# PWM_LED_Controller.net
KiCad netlist of a schematic drawn in EAGLE
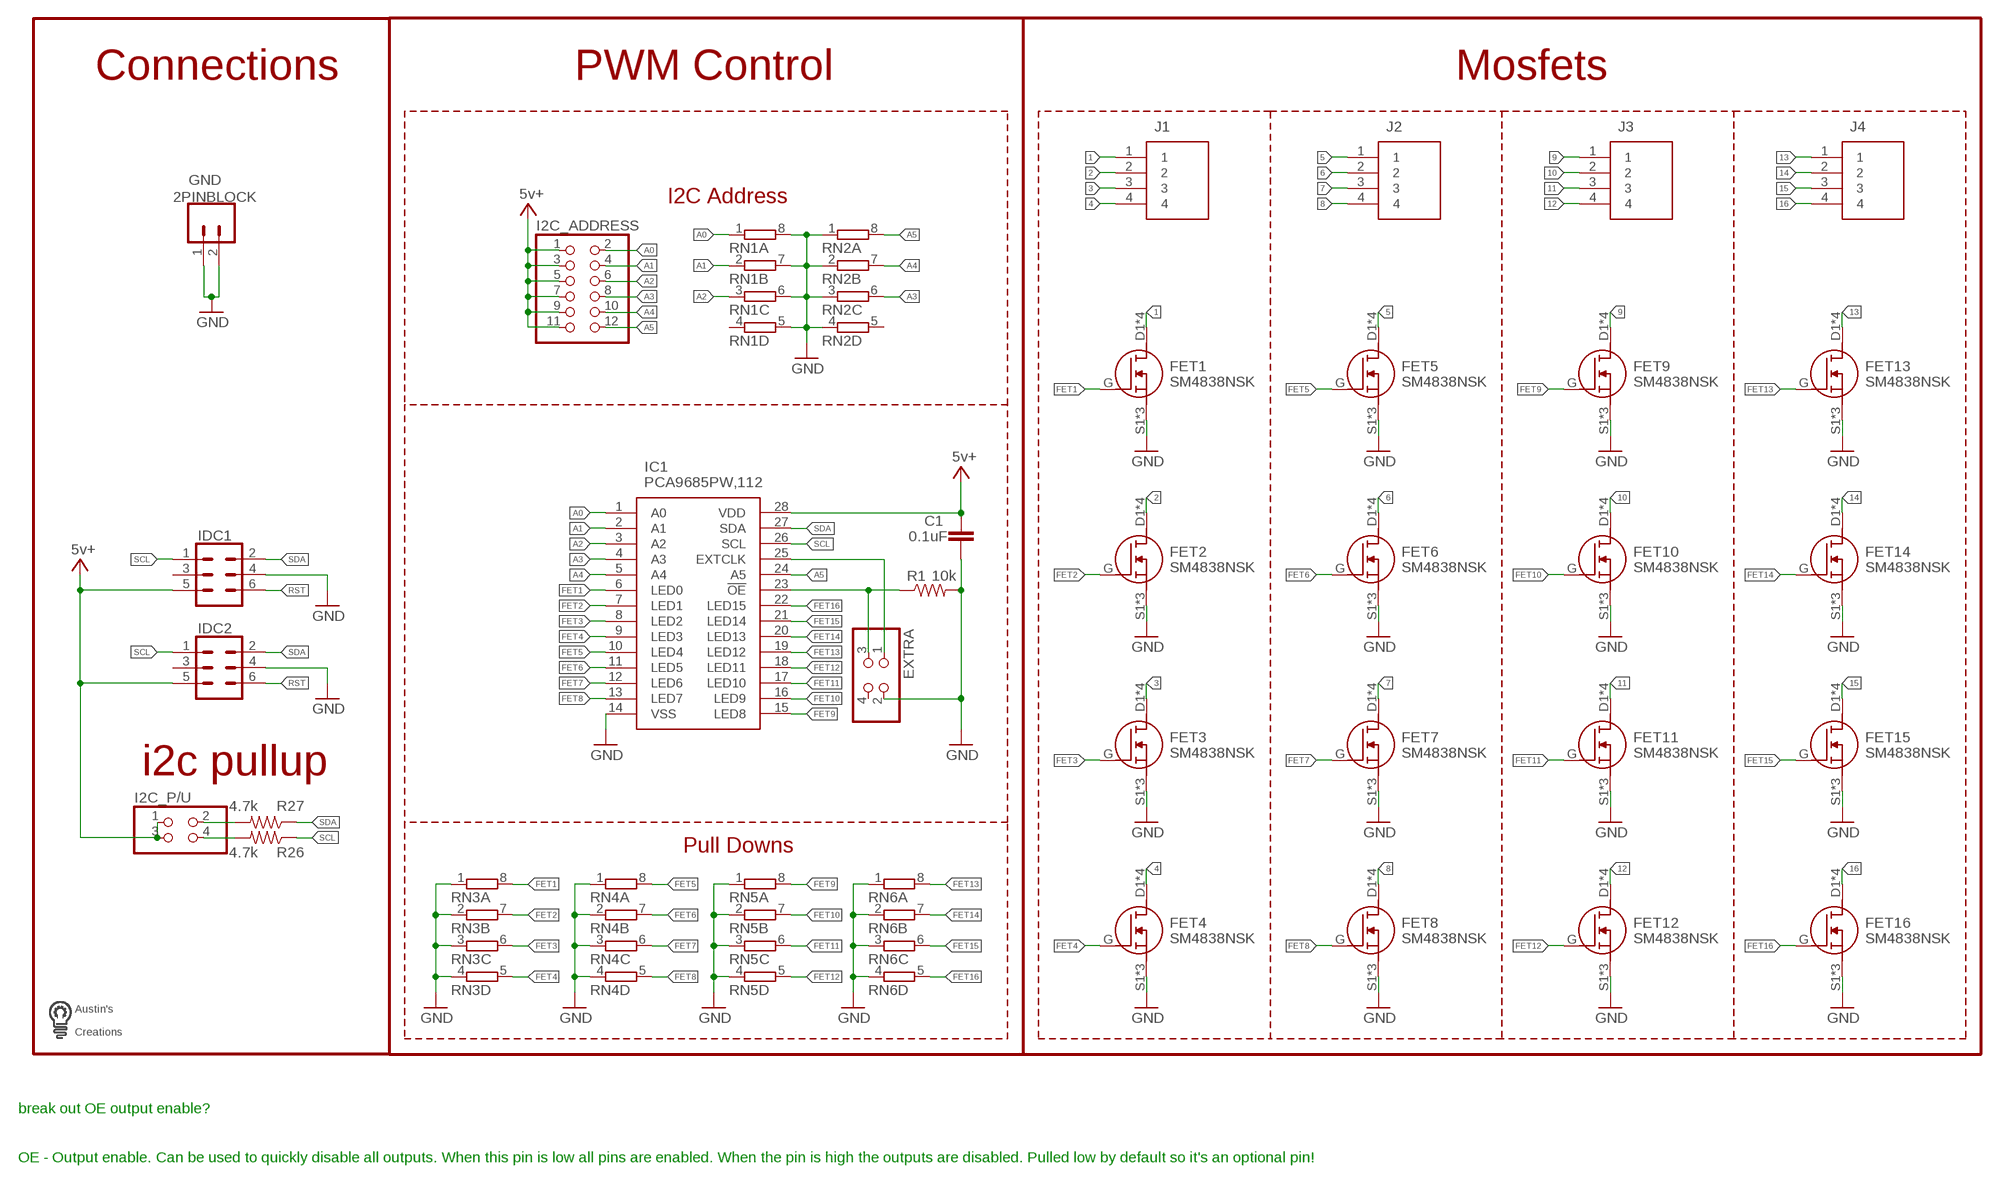
[diagram p0: schematic, sheet 1]

(export (version "E")
  (design (tool "Eeschema 10.0.6"))
  (components
    (comp (ref "C1")
      (value "0.1uF")
      (footprint "eagle-import:C0603")
      (libsource (lib "eagle-import") (part "C-EUC0603"))
    )
    (comp (ref "EXTRA")
      (value "PINHD-2X2")
      (footprint "eagle-import:2X02")
      (libsource (lib "eagle-import") (part "PINHD-2X2"))
    )
    (comp (ref "FET1")
      (value "SM4838NSK")
      (footprint "eagle-import:SM4838NSK")
      (libsource (lib "eagle-import") (part "SM4838NSK"))
    )
    (comp (ref "FET2")
      (value "SM4838NSK")
      (footprint "eagle-import:SM4838NSK")
      (libsource (lib "eagle-import") (part "SM4838NSK"))
    )
    (comp (ref "FET3")
      (value "SM4838NSK")
      (footprint "eagle-import:SM4838NSK")
      (libsource (lib "eagle-import") (part "SM4838NSK"))
    )
    (comp (ref "FET4")
      (value "SM4838NSK")
      (footprint "eagle-import:SM4838NSK")
      (libsource (lib "eagle-import") (part "SM4838NSK"))
    )
    (comp (ref "FET5")
      (value "SM4838NSK")
      (footprint "eagle-import:SM4838NSK")
      (libsource (lib "eagle-import") (part "SM4838NSK"))
    )
    (comp (ref "FET6")
      (value "SM4838NSK")
      (footprint "eagle-import:SM4838NSK")
      (libsource (lib "eagle-import") (part "SM4838NSK"))
    )
    (comp (ref "FET7")
      (value "SM4838NSK")
      (footprint "eagle-import:SM4838NSK")
      (libsource (lib "eagle-import") (part "SM4838NSK"))
    )
    (comp (ref "FET8")
      (value "SM4838NSK")
      (footprint "eagle-import:SM4838NSK")
      (libsource (lib "eagle-import") (part "SM4838NSK"))
    )
    (comp (ref "FET9")
      (value "SM4838NSK")
      (footprint "eagle-import:SM4838NSK")
      (libsource (lib "eagle-import") (part "SM4838NSK"))
    )
    (comp (ref "FET10")
      (value "SM4838NSK")
      (footprint "eagle-import:SM4838NSK")
      (libsource (lib "eagle-import") (part "SM4838NSK"))
    )
    (comp (ref "FET11")
      (value "SM4838NSK")
      (footprint "eagle-import:SM4838NSK")
      (libsource (lib "eagle-import") (part "SM4838NSK"))
    )
    (comp (ref "FET12")
      (value "SM4838NSK")
      (footprint "eagle-import:SM4838NSK")
      (libsource (lib "eagle-import") (part "SM4838NSK"))
    )
    (comp (ref "FET13")
      (value "SM4838NSK")
      (footprint "eagle-import:SM4838NSK")
      (libsource (lib "eagle-import") (part "SM4838NSK"))
    )
    (comp (ref "FET14")
      (value "SM4838NSK")
      (footprint "eagle-import:SM4838NSK")
      (libsource (lib "eagle-import") (part "SM4838NSK"))
    )
    (comp (ref "FET15")
      (value "SM4838NSK")
      (footprint "eagle-import:SM4838NSK")
      (libsource (lib "eagle-import") (part "SM4838NSK"))
    )
    (comp (ref "FET16")
      (value "SM4838NSK")
      (footprint "eagle-import:SM4838NSK")
      (libsource (lib "eagle-import") (part "SM4838NSK"))
    )
    (comp (ref "GND")
      (value "2PINBLOCK")
      (footprint "eagle-import:SCREWTERMINAL-5MM-2")
      (libsource (lib "eagle-import") (part "2PINBLOCK"))
    )
    (comp (ref "I2C_ADDRESS")
      (value "PINHD-2X6")
      (footprint "eagle-import:2X06")
      (libsource (lib "eagle-import") (part "PINHD-2X6"))
    )
    (comp (ref "I2C_P/U")
      (value "PINHD-2X2")
      (footprint "eagle-import:2X02")
      (libsource (lib "eagle-import") (part "PINHD-2X2"))
    )
    (comp (ref "IC1")
      (value "PCA9685PW,112")
      (footprint "eagle-import:SOP65P640X110-28N")
      (fields (field (name "MOUSER_PART_NUMBER") "771-PCA9685PW,112"))
      (libsource (lib "eagle-import") (part "PCA9685PW,112"))
    )
    (comp (ref "IDC1")
      (value "CONN_03X2SHROUD")
      (footprint "eagle-import:2X3-SHROUDED")
      (libsource (lib "eagle-import") (part "CONN_03X2SHROUD"))
    )
    (comp (ref "IDC2")
      (value "CONN_03X2SHROUD")
      (footprint "eagle-import:2X3-SHROUDED")
      (libsource (lib "eagle-import") (part "CONN_03X2SHROUD"))
    )
    (comp (ref "J1")
      (value "SCREWTERMINAL-4P-5MM")
      (footprint "eagle-import:SCREWTERMINAL-4P-5MM")
      (fields
        (field (name "MANUFACTURER_PART_NUMBER") "TB001-500-04BE")
        (field (name "MOUSER_PART_NUMBER") "490-TB001-500-04BE")
      )
      (libsource (lib "eagle-import") (part "SCREWTERMINAL-4P-5MM"))
    )
    (comp (ref "J2")
      (value "SCREWTERMINAL-4P-5MM")
      (footprint "eagle-import:SCREWTERMINAL-4P-5MM")
      (fields
        (field (name "MANUFACTURER_PART_NUMBER") "TB001-500-04BE")
        (field (name "MOUSER_PART_NUMBER") "490-TB001-500-04BE")
      )
      (libsource (lib "eagle-import") (part "SCREWTERMINAL-4P-5MM"))
    )
    (comp (ref "J3")
      (value "SCREWTERMINAL-4P-5MM")
      (footprint "eagle-import:SCREWTERMINAL-4P-5MM")
      (fields
        (field (name "MANUFACTURER_PART_NUMBER") "TB001-500-04BE")
        (field (name "MOUSER_PART_NUMBER") "490-TB001-500-04BE")
      )
      (libsource (lib "eagle-import") (part "SCREWTERMINAL-4P-5MM"))
    )
    (comp (ref "J4")
      (value "SCREWTERMINAL-4P-5MM")
      (footprint "eagle-import:SCREWTERMINAL-4P-5MM")
      (fields
        (field (name "MANUFACTURER_PART_NUMBER") "TB001-500-04BE")
        (field (name "MOUSER_PART_NUMBER") "490-TB001-500-04BE")
      )
      (libsource (lib "eagle-import") (part "SCREWTERMINAL-4P-5MM"))
    )
    (comp (ref "R1")
      (value "10k")
      (footprint "eagle-import:R0603")
      (libsource (lib "eagle-import") (part "R-US_R0603"))
    )
    (comp (ref "R26")
      (value "4.7k")
      (footprint "eagle-import:R0603")
      (libsource (lib "eagle-import") (part "R-US_R0603"))
    )
    (comp (ref "R27")
      (value "4.7k")
      (footprint "eagle-import:R0603")
      (libsource (lib "eagle-import") (part "R-US_R0603"))
    )
    (comp (ref "RN1")
      (value "4R-N0603-ARC")
      (footprint "eagle-import:0603-ARC")
      (libsource (lib "eagle-import") (part "4R-N0603-ARC"))
    )
    (comp (ref "RN2")
      (value "4R-N0603-ARC")
      (footprint "eagle-import:0603-ARC")
      (libsource (lib "eagle-import") (part "4R-N0603-ARC"))
    )
    (comp (ref "RN3")
      (value "4R-N0603-ARC")
      (footprint "eagle-import:0603-ARC")
      (libsource (lib "eagle-import") (part "4R-N0603-ARC"))
    )
    (comp (ref "RN4")
      (value "4R-N0603-ARC")
      (footprint "eagle-import:0603-ARC")
      (libsource (lib "eagle-import") (part "4R-N0603-ARC"))
    )
    (comp (ref "RN5")
      (value "4R-N0603-ARC")
      (footprint "eagle-import:0603-ARC")
      (libsource (lib "eagle-import") (part "4R-N0603-ARC"))
    )
    (comp (ref "RN6")
      (value "4R-N0603-ARC")
      (footprint "eagle-import:0603-ARC")
      (libsource (lib "eagle-import") (part "4R-N0603-ARC"))
    )
    (comp (ref "U$1")
      (value "LOGOMED")
      (footprint "eagle-import:LOGOMED")
      (libsource (lib "eagle-import") (part "LOGOMED"))
    )
  )
  (nets
    (net (code "1") (name "1") (class "Default")
      (node (ref "FET1") (pin "D1") (pinfunction "D_D1") (pintype "bidirectional"))
      (node (ref "FET1") (pin "D2") (pinfunction "D_D2") (pintype "bidirectional"))
      (node (ref "FET1") (pin "D3") (pinfunction "D_D3") (pintype "bidirectional"))
      (node (ref "FET1") (pin "D4") (pinfunction "D_D4") (pintype "bidirectional"))
      (node (ref "J1") (pin "1") (pinfunction "1_1") (pintype "bidirectional"))
    )
    (net (code "2") (name "2") (class "Default")
      (node (ref "FET2") (pin "D1") (pinfunction "D_D1") (pintype "bidirectional"))
      (node (ref "FET2") (pin "D2") (pinfunction "D_D2") (pintype "bidirectional"))
      (node (ref "FET2") (pin "D3") (pinfunction "D_D3") (pintype "bidirectional"))
      (node (ref "FET2") (pin "D4") (pinfunction "D_D4") (pintype "bidirectional"))
      (node (ref "J1") (pin "2") (pinfunction "2_2") (pintype "bidirectional"))
    )
    (net (code "3") (name "3") (class "Default")
      (node (ref "FET3") (pin "D1") (pinfunction "D_D1") (pintype "bidirectional"))
      (node (ref "FET3") (pin "D2") (pinfunction "D_D2") (pintype "bidirectional"))
      (node (ref "FET3") (pin "D3") (pinfunction "D_D3") (pintype "bidirectional"))
      (node (ref "FET3") (pin "D4") (pinfunction "D_D4") (pintype "bidirectional"))
      (node (ref "J1") (pin "3") (pinfunction "3_3") (pintype "bidirectional"))
    )
    (net (code "4") (name "4") (class "Default")
      (node (ref "FET4") (pin "D1") (pinfunction "D_D1") (pintype "bidirectional"))
      (node (ref "FET4") (pin "D2") (pinfunction "D_D2") (pintype "bidirectional"))
      (node (ref "FET4") (pin "D3") (pinfunction "D_D3") (pintype "bidirectional"))
      (node (ref "FET4") (pin "D4") (pinfunction "D_D4") (pintype "bidirectional"))
      (node (ref "J1") (pin "4") (pinfunction "4_4") (pintype "bidirectional"))
    )
    (net (code "5") (name "5") (class "Default")
      (node (ref "FET5") (pin "D1") (pinfunction "D_D1") (pintype "bidirectional"))
      (node (ref "FET5") (pin "D2") (pinfunction "D_D2") (pintype "bidirectional"))
      (node (ref "FET5") (pin "D3") (pinfunction "D_D3") (pintype "bidirectional"))
      (node (ref "FET5") (pin "D4") (pinfunction "D_D4") (pintype "bidirectional"))
      (node (ref "J2") (pin "1") (pinfunction "1_1") (pintype "bidirectional"))
    )
    (net (code "6") (name "5v+") (class "Default")
      (node (ref "C1") (pin "1") (pinfunction "1_1") (pintype "passive"))
      (node (ref "I2C_ADDRESS") (pin "1") (pinfunction "1_1") (pintype "passive"))
      (node (ref "I2C_ADDRESS") (pin "11") (pinfunction "11_11") (pintype "passive"))
      (node (ref "I2C_ADDRESS") (pin "3") (pinfunction "3_3") (pintype "passive"))
      (node (ref "I2C_ADDRESS") (pin "5") (pinfunction "5_5") (pintype "passive"))
      (node (ref "I2C_ADDRESS") (pin "7") (pinfunction "7_7") (pintype "passive"))
      (node (ref "I2C_ADDRESS") (pin "9") (pinfunction "9_9") (pintype "passive"))
      (node (ref "I2C_P/U") (pin "1") (pinfunction "1_1") (pintype "passive"))
      (node (ref "I2C_P/U") (pin "3") (pinfunction "3_3") (pintype "passive"))
      (node (ref "IC1") (pin "28") (pinfunction "VDD_28") (pintype "bidirectional"))
      (node (ref "IDC1") (pin "5") (pinfunction "5_5") (pintype "bidirectional"))
      (node (ref "IDC2") (pin "5") (pinfunction "5_5") (pintype "bidirectional"))
    )
    (net (code "7") (name "6") (class "Default")
      (node (ref "FET6") (pin "D1") (pinfunction "D_D1") (pintype "bidirectional"))
      (node (ref "FET6") (pin "D2") (pinfunction "D_D2") (pintype "bidirectional"))
      (node (ref "FET6") (pin "D3") (pinfunction "D_D3") (pintype "bidirectional"))
      (node (ref "FET6") (pin "D4") (pinfunction "D_D4") (pintype "bidirectional"))
      (node (ref "J2") (pin "2") (pinfunction "2_2") (pintype "bidirectional"))
    )
    (net (code "8") (name "7") (class "Default")
      (node (ref "FET7") (pin "D1") (pinfunction "D_D1") (pintype "bidirectional"))
      (node (ref "FET7") (pin "D2") (pinfunction "D_D2") (pintype "bidirectional"))
      (node (ref "FET7") (pin "D3") (pinfunction "D_D3") (pintype "bidirectional"))
      (node (ref "FET7") (pin "D4") (pinfunction "D_D4") (pintype "bidirectional"))
      (node (ref "J2") (pin "3") (pinfunction "3_3") (pintype "bidirectional"))
    )
    (net (code "9") (name "8") (class "Default")
      (node (ref "FET8") (pin "D1") (pinfunction "D_D1") (pintype "bidirectional"))
      (node (ref "FET8") (pin "D2") (pinfunction "D_D2") (pintype "bidirectional"))
      (node (ref "FET8") (pin "D3") (pinfunction "D_D3") (pintype "bidirectional"))
      (node (ref "FET8") (pin "D4") (pinfunction "D_D4") (pintype "bidirectional"))
      (node (ref "J2") (pin "4") (pinfunction "4_4") (pintype "bidirectional"))
    )
    (net (code "10") (name "9") (class "Default")
      (node (ref "FET9") (pin "D1") (pinfunction "D_D1") (pintype "bidirectional"))
      (node (ref "FET9") (pin "D2") (pinfunction "D_D2") (pintype "bidirectional"))
      (node (ref "FET9") (pin "D3") (pinfunction "D_D3") (pintype "bidirectional"))
      (node (ref "FET9") (pin "D4") (pinfunction "D_D4") (pintype "bidirectional"))
      (node (ref "J3") (pin "1") (pinfunction "1_1") (pintype "bidirectional"))
    )
    (net (code "11") (name "10") (class "Default")
      (node (ref "FET10") (pin "D1") (pinfunction "D_D1") (pintype "bidirectional"))
      (node (ref "FET10") (pin "D2") (pinfunction "D_D2") (pintype "bidirectional"))
      (node (ref "FET10") (pin "D3") (pinfunction "D_D3") (pintype "bidirectional"))
      (node (ref "FET10") (pin "D4") (pinfunction "D_D4") (pintype "bidirectional"))
      (node (ref "J3") (pin "2") (pinfunction "2_2") (pintype "bidirectional"))
    )
    (net (code "12") (name "11") (class "Default")
      (node (ref "FET11") (pin "D1") (pinfunction "D_D1") (pintype "bidirectional"))
      (node (ref "FET11") (pin "D2") (pinfunction "D_D2") (pintype "bidirectional"))
      (node (ref "FET11") (pin "D3") (pinfunction "D_D3") (pintype "bidirectional"))
      (node (ref "FET11") (pin "D4") (pinfunction "D_D4") (pintype "bidirectional"))
      (node (ref "J3") (pin "3") (pinfunction "3_3") (pintype "bidirectional"))
    )
    (net (code "13") (name "12") (class "Default")
      (node (ref "FET12") (pin "D1") (pinfunction "D_D1") (pintype "bidirectional"))
      (node (ref "FET12") (pin "D2") (pinfunction "D_D2") (pintype "bidirectional"))
      (node (ref "FET12") (pin "D3") (pinfunction "D_D3") (pintype "bidirectional"))
      (node (ref "FET12") (pin "D4") (pinfunction "D_D4") (pintype "bidirectional"))
      (node (ref "J3") (pin "4") (pinfunction "4_4") (pintype "bidirectional"))
    )
    (net (code "14") (name "13") (class "Default")
      (node (ref "FET13") (pin "D1") (pinfunction "D_D1") (pintype "bidirectional"))
      (node (ref "FET13") (pin "D2") (pinfunction "D_D2") (pintype "bidirectional"))
      (node (ref "FET13") (pin "D3") (pinfunction "D_D3") (pintype "bidirectional"))
      (node (ref "FET13") (pin "D4") (pinfunction "D_D4") (pintype "bidirectional"))
      (node (ref "J4") (pin "1") (pinfunction "1_1") (pintype "bidirectional"))
    )
    (net (code "15") (name "14") (class "Default")
      (node (ref "FET14") (pin "D1") (pinfunction "D_D1") (pintype "bidirectional"))
      (node (ref "FET14") (pin "D2") (pinfunction "D_D2") (pintype "bidirectional"))
      (node (ref "FET14") (pin "D3") (pinfunction "D_D3") (pintype "bidirectional"))
      (node (ref "FET14") (pin "D4") (pinfunction "D_D4") (pintype "bidirectional"))
      (node (ref "J4") (pin "2") (pinfunction "2_2") (pintype "bidirectional"))
    )
    (net (code "16") (name "15") (class "Default")
      (node (ref "FET15") (pin "D1") (pinfunction "D_D1") (pintype "bidirectional"))
      (node (ref "FET15") (pin "D2") (pinfunction "D_D2") (pintype "bidirectional"))
      (node (ref "FET15") (pin "D3") (pinfunction "D_D3") (pintype "bidirectional"))
      (node (ref "FET15") (pin "D4") (pinfunction "D_D4") (pintype "bidirectional"))
      (node (ref "J4") (pin "3") (pinfunction "3_3") (pintype "bidirectional"))
    )
    (net (code "17") (name "16") (class "Default")
      (node (ref "FET16") (pin "D1") (pinfunction "D_D1") (pintype "bidirectional"))
      (node (ref "FET16") (pin "D2") (pinfunction "D_D2") (pintype "bidirectional"))
      (node (ref "FET16") (pin "D3") (pinfunction "D_D3") (pintype "bidirectional"))
      (node (ref "FET16") (pin "D4") (pinfunction "D_D4") (pintype "bidirectional"))
      (node (ref "J4") (pin "4") (pinfunction "4_4") (pintype "bidirectional"))
    )
    (net (code "18") (name "A0") (class "Default")
      (node (ref "I2C_ADDRESS") (pin "2") (pinfunction "2_2") (pintype "passive"))
      (node (ref "IC1") (pin "1") (pinfunction "A0_1") (pintype "bidirectional"))
      (node (ref "RN1") (pin "1") (pinfunction "1_1") (pintype "passive"))
    )
    (net (code "19") (name "A1") (class "Default")
      (node (ref "I2C_ADDRESS") (pin "4") (pinfunction "4_4") (pintype "passive"))
      (node (ref "IC1") (pin "2") (pinfunction "A1_2") (pintype "bidirectional"))
      (node (ref "RN1") (pin "2") (pinfunction "1_2") (pintype "passive"))
    )
    (net (code "20") (name "A2") (class "Default")
      (node (ref "I2C_ADDRESS") (pin "6") (pinfunction "6_6") (pintype "passive"))
      (node (ref "IC1") (pin "3") (pinfunction "A2_3") (pintype "bidirectional"))
      (node (ref "RN1") (pin "3") (pinfunction "1_3") (pintype "passive"))
    )
    (net (code "21") (name "A3") (class "Default")
      (node (ref "I2C_ADDRESS") (pin "8") (pinfunction "8_8") (pintype "passive"))
      (node (ref "IC1") (pin "4") (pinfunction "A3_4") (pintype "bidirectional"))
      (node (ref "RN2") (pin "6") (pinfunction "2_6") (pintype "passive"))
    )
    (net (code "22") (name "A4") (class "Default")
      (node (ref "I2C_ADDRESS") (pin "10") (pinfunction "10_10") (pintype "passive"))
      (node (ref "IC1") (pin "5") (pinfunction "A4_5") (pintype "bidirectional"))
      (node (ref "RN2") (pin "7") (pinfunction "2_7") (pintype "passive"))
    )
    (net (code "23") (name "A5") (class "Default")
      (node (ref "I2C_ADDRESS") (pin "12") (pinfunction "12_12") (pintype "passive"))
      (node (ref "IC1") (pin "24") (pinfunction "A5_24") (pintype "bidirectional"))
      (node (ref "RN2") (pin "8") (pinfunction "2_8") (pintype "passive"))
    )
    (net (code "24") (name "FET1") (class "Default")
      (node (ref "FET1") (pin "G") (pinfunction "G_G") (pintype "bidirectional"))
      (node (ref "IC1") (pin "6") (pinfunction "LED0_6") (pintype "bidirectional"))
      (node (ref "RN3") (pin "8") (pinfunction "2_8") (pintype "passive"))
    )
    (net (code "25") (name "FET2") (class "Default")
      (node (ref "FET2") (pin "G") (pinfunction "G_G") (pintype "bidirectional"))
      (node (ref "IC1") (pin "7") (pinfunction "LED1_7") (pintype "bidirectional"))
      (node (ref "RN3") (pin "7") (pinfunction "2_7") (pintype "passive"))
    )
    (net (code "26") (name "FET3") (class "Default")
      (node (ref "FET3") (pin "G") (pinfunction "G_G") (pintype "bidirectional"))
      (node (ref "IC1") (pin "8") (pinfunction "LED2_8") (pintype "bidirectional"))
      (node (ref "RN3") (pin "6") (pinfunction "2_6") (pintype "passive"))
    )
    (net (code "27") (name "FET4") (class "Default")
      (node (ref "FET4") (pin "G") (pinfunction "G_G") (pintype "bidirectional"))
      (node (ref "IC1") (pin "9") (pinfunction "LED3_9") (pintype "bidirectional"))
      (node (ref "RN3") (pin "5") (pinfunction "2_5") (pintype "passive"))
    )
    (net (code "28") (name "FET5") (class "Default")
      (node (ref "FET5") (pin "G") (pinfunction "G_G") (pintype "bidirectional"))
      (node (ref "IC1") (pin "10") (pinfunction "LED4_10") (pintype "bidirectional"))
      (node (ref "RN4") (pin "8") (pinfunction "2_8") (pintype "passive"))
    )
    (net (code "29") (name "FET6") (class "Default")
      (node (ref "FET6") (pin "G") (pinfunction "G_G") (pintype "bidirectional"))
      (node (ref "IC1") (pin "11") (pinfunction "LED5_11") (pintype "bidirectional"))
      (node (ref "RN4") (pin "7") (pinfunction "2_7") (pintype "passive"))
    )
    (net (code "30") (name "FET7") (class "Default")
      (node (ref "FET7") (pin "G") (pinfunction "G_G") (pintype "bidirectional"))
      (node (ref "IC1") (pin "12") (pinfunction "LED6_12") (pintype "bidirectional"))
      (node (ref "RN4") (pin "6") (pinfunction "2_6") (pintype "passive"))
    )
    (net (code "31") (name "FET8") (class "Default")
      (node (ref "FET8") (pin "G") (pinfunction "G_G") (pintype "bidirectional"))
      (node (ref "IC1") (pin "13") (pinfunction "LED7_13") (pintype "bidirectional"))
      (node (ref "RN4") (pin "5") (pinfunction "2_5") (pintype "passive"))
    )
    (net (code "32") (name "FET9") (class "Default")
      (node (ref "FET9") (pin "G") (pinfunction "G_G") (pintype "bidirectional"))
      (node (ref "IC1") (pin "15") (pinfunction "LED8_15") (pintype "bidirectional"))
      (node (ref "RN5") (pin "8") (pinfunction "2_8") (pintype "passive"))
    )
    (net (code "33") (name "FET10") (class "Default")
      (node (ref "FET10") (pin "G") (pinfunction "G_G") (pintype "bidirectional"))
      (node (ref "IC1") (pin "16") (pinfunction "LED9_16") (pintype "bidirectional"))
      (node (ref "RN5") (pin "7") (pinfunction "2_7") (pintype "passive"))
    )
    (net (code "34") (name "FET11") (class "Default")
      (node (ref "FET11") (pin "G") (pinfunction "G_G") (pintype "bidirectional"))
      (node (ref "IC1") (pin "17") (pinfunction "LED10_17") (pintype "bidirectional"))
      (node (ref "RN5") (pin "6") (pinfunction "2_6") (pintype "passive"))
    )
    (net (code "35") (name "FET12") (class "Default")
      (node (ref "FET12") (pin "G") (pinfunction "G_G") (pintype "bidirectional"))
      (node (ref "IC1") (pin "18") (pinfunction "LED11_18") (pintype "bidirectional"))
      (node (ref "RN5") (pin "5") (pinfunction "2_5") (pintype "passive"))
    )
    (net (code "36") (name "FET13") (class "Default")
      (node (ref "FET13") (pin "G") (pinfunction "G_G") (pintype "bidirectional"))
      (node (ref "IC1") (pin "19") (pinfunction "LED12_19") (pintype "bidirectional"))
      (node (ref "RN6") (pin "8") (pinfunction "2_8") (pintype "passive"))
    )
    (net (code "37") (name "FET14") (class "Default")
      (node (ref "FET14") (pin "G") (pinfunction "G_G") (pintype "bidirectional"))
      (node (ref "IC1") (pin "20") (pinfunction "LED13_20") (pintype "bidirectional"))
      (node (ref "RN6") (pin "7") (pinfunction "2_7") (pintype "passive"))
    )
    (net (code "38") (name "FET15") (class "Default")
      (node (ref "FET15") (pin "G") (pinfunction "G_G") (pintype "bidirectional"))
      (node (ref "IC1") (pin "21") (pinfunction "LED14_21") (pintype "bidirectional"))
      (node (ref "RN6") (pin "6") (pinfunction "2_6") (pintype "passive"))
    )
    (net (code "39") (name "FET16") (class "Default")
      (node (ref "FET16") (pin "G") (pinfunction "G_G") (pintype "bidirectional"))
      (node (ref "IC1") (pin "22") (pinfunction "LED15_22") (pintype "bidirectional"))
      (node (ref "RN6") (pin "5") (pinfunction "2_5") (pintype "passive"))
    )
    (net (code "40") (name "GND") (class "Default")
      (node (ref "C1") (pin "2") (pinfunction "2_2") (pintype "passive"))
      (node (ref "EXTRA") (pin "2") (pinfunction "2_2") (pintype "passive"))
      (node (ref "FET1") (pin "S1") (pinfunction "S_S1") (pintype "bidirectional"))
      (node (ref "FET1") (pin "S2") (pinfunction "S_S2") (pintype "bidirectional"))
      (node (ref "FET1") (pin "S3") (pinfunction "S_S3") (pintype "bidirectional"))
      (node (ref "FET10") (pin "S1") (pinfunction "S_S1") (pintype "bidirectional"))
      (node (ref "FET10") (pin "S2") (pinfunction "S_S2") (pintype "bidirectional"))
      (node (ref "FET10") (pin "S3") (pinfunction "S_S3") (pintype "bidirectional"))
      (node (ref "FET11") (pin "S1") (pinfunction "S_S1") (pintype "bidirectional"))
      (node (ref "FET11") (pin "S2") (pinfunction "S_S2") (pintype "bidirectional"))
      (node (ref "FET11") (pin "S3") (pinfunction "S_S3") (pintype "bidirectional"))
      (node (ref "FET12") (pin "S1") (pinfunction "S_S1") (pintype "bidirectional"))
      (node (ref "FET12") (pin "S2") (pinfunction "S_S2") (pintype "bidirectional"))
      (node (ref "FET12") (pin "S3") (pinfunction "S_S3") (pintype "bidirectional"))
      (node (ref "FET13") (pin "S1") (pinfunction "S_S1") (pintype "bidirectional"))
      (node (ref "FET13") (pin "S2") (pinfunction "S_S2") (pintype "bidirectional"))
      (node (ref "FET13") (pin "S3") (pinfunction "S_S3") (pintype "bidirectional"))
      (node (ref "FET14") (pin "S1") (pinfunction "S_S1") (pintype "bidirectional"))
      (node (ref "FET14") (pin "S2") (pinfunction "S_S2") (pintype "bidirectional"))
      (node (ref "FET14") (pin "S3") (pinfunction "S_S3") (pintype "bidirectional"))
      (node (ref "FET15") (pin "S1") (pinfunction "S_S1") (pintype "bidirectional"))
      (node (ref "FET15") (pin "S2") (pinfunction "S_S2") (pintype "bidirectional"))
      (node (ref "FET15") (pin "S3") (pinfunction "S_S3") (pintype "bidirectional"))
      (node (ref "FET16") (pin "S1") (pinfunction "S_S1") (pintype "bidirectional"))
      (node (ref "FET16") (pin "S2") (pinfunction "S_S2") (pintype "bidirectional"))
      (node (ref "FET16") (pin "S3") (pinfunction "S_S3") (pintype "bidirectional"))
      (node (ref "FET2") (pin "S1") (pinfunction "S_S1") (pintype "bidirectional"))
      (node (ref "FET2") (pin "S2") (pinfunction "S_S2") (pintype "bidirectional"))
      (node (ref "FET2") (pin "S3") (pinfunction "S_S3") (pintype "bidirectional"))
      (node (ref "FET3") (pin "S1") (pinfunction "S_S1") (pintype "bidirectional"))
      (node (ref "FET3") (pin "S2") (pinfunction "S_S2") (pintype "bidirectional"))
      (node (ref "FET3") (pin "S3") (pinfunction "S_S3") (pintype "bidirectional"))
      (node (ref "FET4") (pin "S1") (pinfunction "S_S1") (pintype "bidirectional"))
      (node (ref "FET4") (pin "S2") (pinfunction "S_S2") (pintype "bidirectional"))
      (node (ref "FET4") (pin "S3") (pinfunction "S_S3") (pintype "bidirectional"))
      (node (ref "FET5") (pin "S1") (pinfunction "S_S1") (pintype "bidirectional"))
      (node (ref "FET5") (pin "S2") (pinfunction "S_S2") (pintype "bidirectional"))
      (node (ref "FET5") (pin "S3") (pinfunction "S_S3") (pintype "bidirectional"))
      (node (ref "FET6") (pin "S1") (pinfunction "S_S1") (pintype "bidirectional"))
      (node (ref "FET6") (pin "S2") (pinfunction "S_S2") (pintype "bidirectional"))
      (node (ref "FET6") (pin "S3") (pinfunction "S_S3") (pintype "bidirectional"))
      (node (ref "FET7") (pin "S1") (pinfunction "S_S1") (pintype "bidirectional"))
      (node (ref "FET7") (pin "S2") (pinfunction "S_S2") (pintype "bidirectional"))
      (node (ref "FET7") (pin "S3") (pinfunction "S_S3") (pintype "bidirectional"))
      (node (ref "FET8") (pin "S1") (pinfunction "S_S1") (pintype "bidirectional"))
      (node (ref "FET8") (pin "S2") (pinfunction "S_S2") (pintype "bidirectional"))
      (node (ref "FET8") (pin "S3") (pinfunction "S_S3") (pintype "bidirectional"))
      (node (ref "FET9") (pin "S1") (pinfunction "S_S1") (pintype "bidirectional"))
      (node (ref "FET9") (pin "S2") (pinfunction "S_S2") (pintype "bidirectional"))
      (node (ref "FET9") (pin "S3") (pinfunction "S_S3") (pintype "bidirectional"))
      (node (ref "GND") (pin "1") (pinfunction "1_1") (pintype "passive"))
      (node (ref "GND") (pin "2") (pinfunction "2_2") (pintype "passive"))
      (node (ref "IC1") (pin "14") (pinfunction "VSS_14") (pintype "bidirectional"))
      (node (ref "IDC1") (pin "4") (pinfunction "4_4") (pintype "bidirectional"))
      (node (ref "IDC2") (pin "4") (pinfunction "4_4") (pintype "bidirectional"))
      (node (ref "R1") (pin "2") (pinfunction "2_2") (pintype "passive"))
      (node (ref "RN1") (pin "5") (pinfunction "2_5") (pintype "passive"))
      (node (ref "RN1") (pin "6") (pinfunction "2_6") (pintype "passive"))
      (node (ref "RN1") (pin "7") (pinfunction "2_7") (pintype "passive"))
      (node (ref "RN1") (pin "8") (pinfunction "2_8") (pintype "passive"))
      (node (ref "RN2") (pin "1") (pinfunction "1_1") (pintype "passive"))
      (node (ref "RN2") (pin "2") (pinfunction "1_2") (pintype "passive"))
      (node (ref "RN2") (pin "3") (pinfunction "1_3") (pintype "passive"))
      (node (ref "RN2") (pin "4") (pinfunction "1_4") (pintype "passive"))
      (node (ref "RN3") (pin "1") (pinfunction "1_1") (pintype "passive"))
      (node (ref "RN3") (pin "2") (pinfunction "1_2") (pintype "passive"))
      (node (ref "RN3") (pin "3") (pinfunction "1_3") (pintype "passive"))
      (node (ref "RN3") (pin "4") (pinfunction "1_4") (pintype "passive"))
      (node (ref "RN4") (pin "1") (pinfunction "1_1") (pintype "passive"))
      (node (ref "RN4") (pin "2") (pinfunction "1_2") (pintype "passive"))
      (node (ref "RN4") (pin "3") (pinfunction "1_3") (pintype "passive"))
      (node (ref "RN4") (pin "4") (pinfunction "1_4") (pintype "passive"))
      (node (ref "RN5") (pin "1") (pinfunction "1_1") (pintype "passive"))
      (node (ref "RN5") (pin "2") (pinfunction "1_2") (pintype "passive"))
      (node (ref "RN5") (pin "3") (pinfunction "1_3") (pintype "passive"))
      (node (ref "RN5") (pin "4") (pinfunction "1_4") (pintype "passive"))
      (node (ref "RN6") (pin "1") (pinfunction "1_1") (pintype "passive"))
      (node (ref "RN6") (pin "2") (pinfunction "1_2") (pintype "passive"))
      (node (ref "RN6") (pin "3") (pinfunction "1_3") (pintype "passive"))
      (node (ref "RN6") (pin "4") (pinfunction "1_4") (pintype "passive"))
    )
    (net (code "41") (name "Net-(I2C_P/U-Pad2)") (class "Default")
      (node (ref "I2C_P/U") (pin "2") (pinfunction "2_2") (pintype "passive"))
      (node (ref "R27") (pin "2") (pinfunction "2_2") (pintype "passive"))
    )
    (net (code "42") (name "Net-(I2C_P/U-Pad4)") (class "Default")
      (node (ref "I2C_P/U") (pin "4") (pinfunction "4_4") (pintype "passive"))
      (node (ref "R26") (pin "2") (pinfunction "2_2") (pintype "passive"))
    )
    (net (code "43") (name "Net-(IC1-EXTCLK)") (class "Default")
      (node (ref "EXTRA") (pin "1") (pinfunction "1_1") (pintype "passive"))
      (node (ref "IC1") (pin "25") (pinfunction "EXTCLK_25") (pintype "bidirectional"))
    )
    (net (code "44") (name "Net-(IC1-~{OE})") (class "Default")
      (node (ref "EXTRA") (pin "3") (pinfunction "3_3") (pintype "passive"))
      (node (ref "IC1") (pin "23") (pinfunction "~{OE}_23") (pintype "bidirectional"))
      (node (ref "R1") (pin "1") (pinfunction "1_1") (pintype "passive"))
    )
    (net (code "45") (name "RST") (class "Default")
      (node (ref "IDC1") (pin "6") (pinfunction "6_6") (pintype "bidirectional"))
      (node (ref "IDC2") (pin "6") (pinfunction "6_6") (pintype "bidirectional"))
    )
    (net (code "46") (name "SCL") (class "Default")
      (node (ref "IC1") (pin "26") (pinfunction "SCL_26") (pintype "bidirectional"))
      (node (ref "IDC1") (pin "1") (pinfunction "1_1") (pintype "bidirectional"))
      (node (ref "IDC2") (pin "1") (pinfunction "1_1") (pintype "bidirectional"))
      (node (ref "R26") (pin "1") (pinfunction "1_1") (pintype "passive"))
    )
    (net (code "47") (name "SDA") (class "Default")
      (node (ref "IC1") (pin "27") (pinfunction "SDA_27") (pintype "bidirectional"))
      (node (ref "IDC1") (pin "2") (pinfunction "2_2") (pintype "bidirectional"))
      (node (ref "IDC2") (pin "2") (pinfunction "2_2") (pintype "bidirectional"))
      (node (ref "R27") (pin "1") (pinfunction "1_1") (pintype "passive"))
    )
    (net (code "48") (name "unconnected-(EXTRA-Pad4)") (class "Default")
      (node (ref "EXTRA") (pin "4") (pinfunction "4_4") (pintype "passive"))
    )
    (net (code "49") (name "unconnected-(IDC1-Pad3)") (class "Default")
      (node (ref "IDC1") (pin "3") (pinfunction "3_3") (pintype "bidirectional"))
    )
    (net (code "50") (name "unconnected-(IDC2-Pad3)") (class "Default")
      (node (ref "IDC2") (pin "3") (pinfunction "3_3") (pintype "bidirectional"))
    )
    (net (code "51") (name "unconnected-(RN1D-1-Pad4)") (class "Default")
      (node (ref "RN1") (pin "4") (pinfunction "1_4") (pintype "passive"))
    )
    (net (code "52") (name "unconnected-(RN2D-2-Pad5)") (class "Default")
      (node (ref "RN2") (pin "5") (pinfunction "2_5") (pintype "passive"))
    )
  )
)
